# ADC.net
KiCad netlist of a schematic drawn in Altium Designer
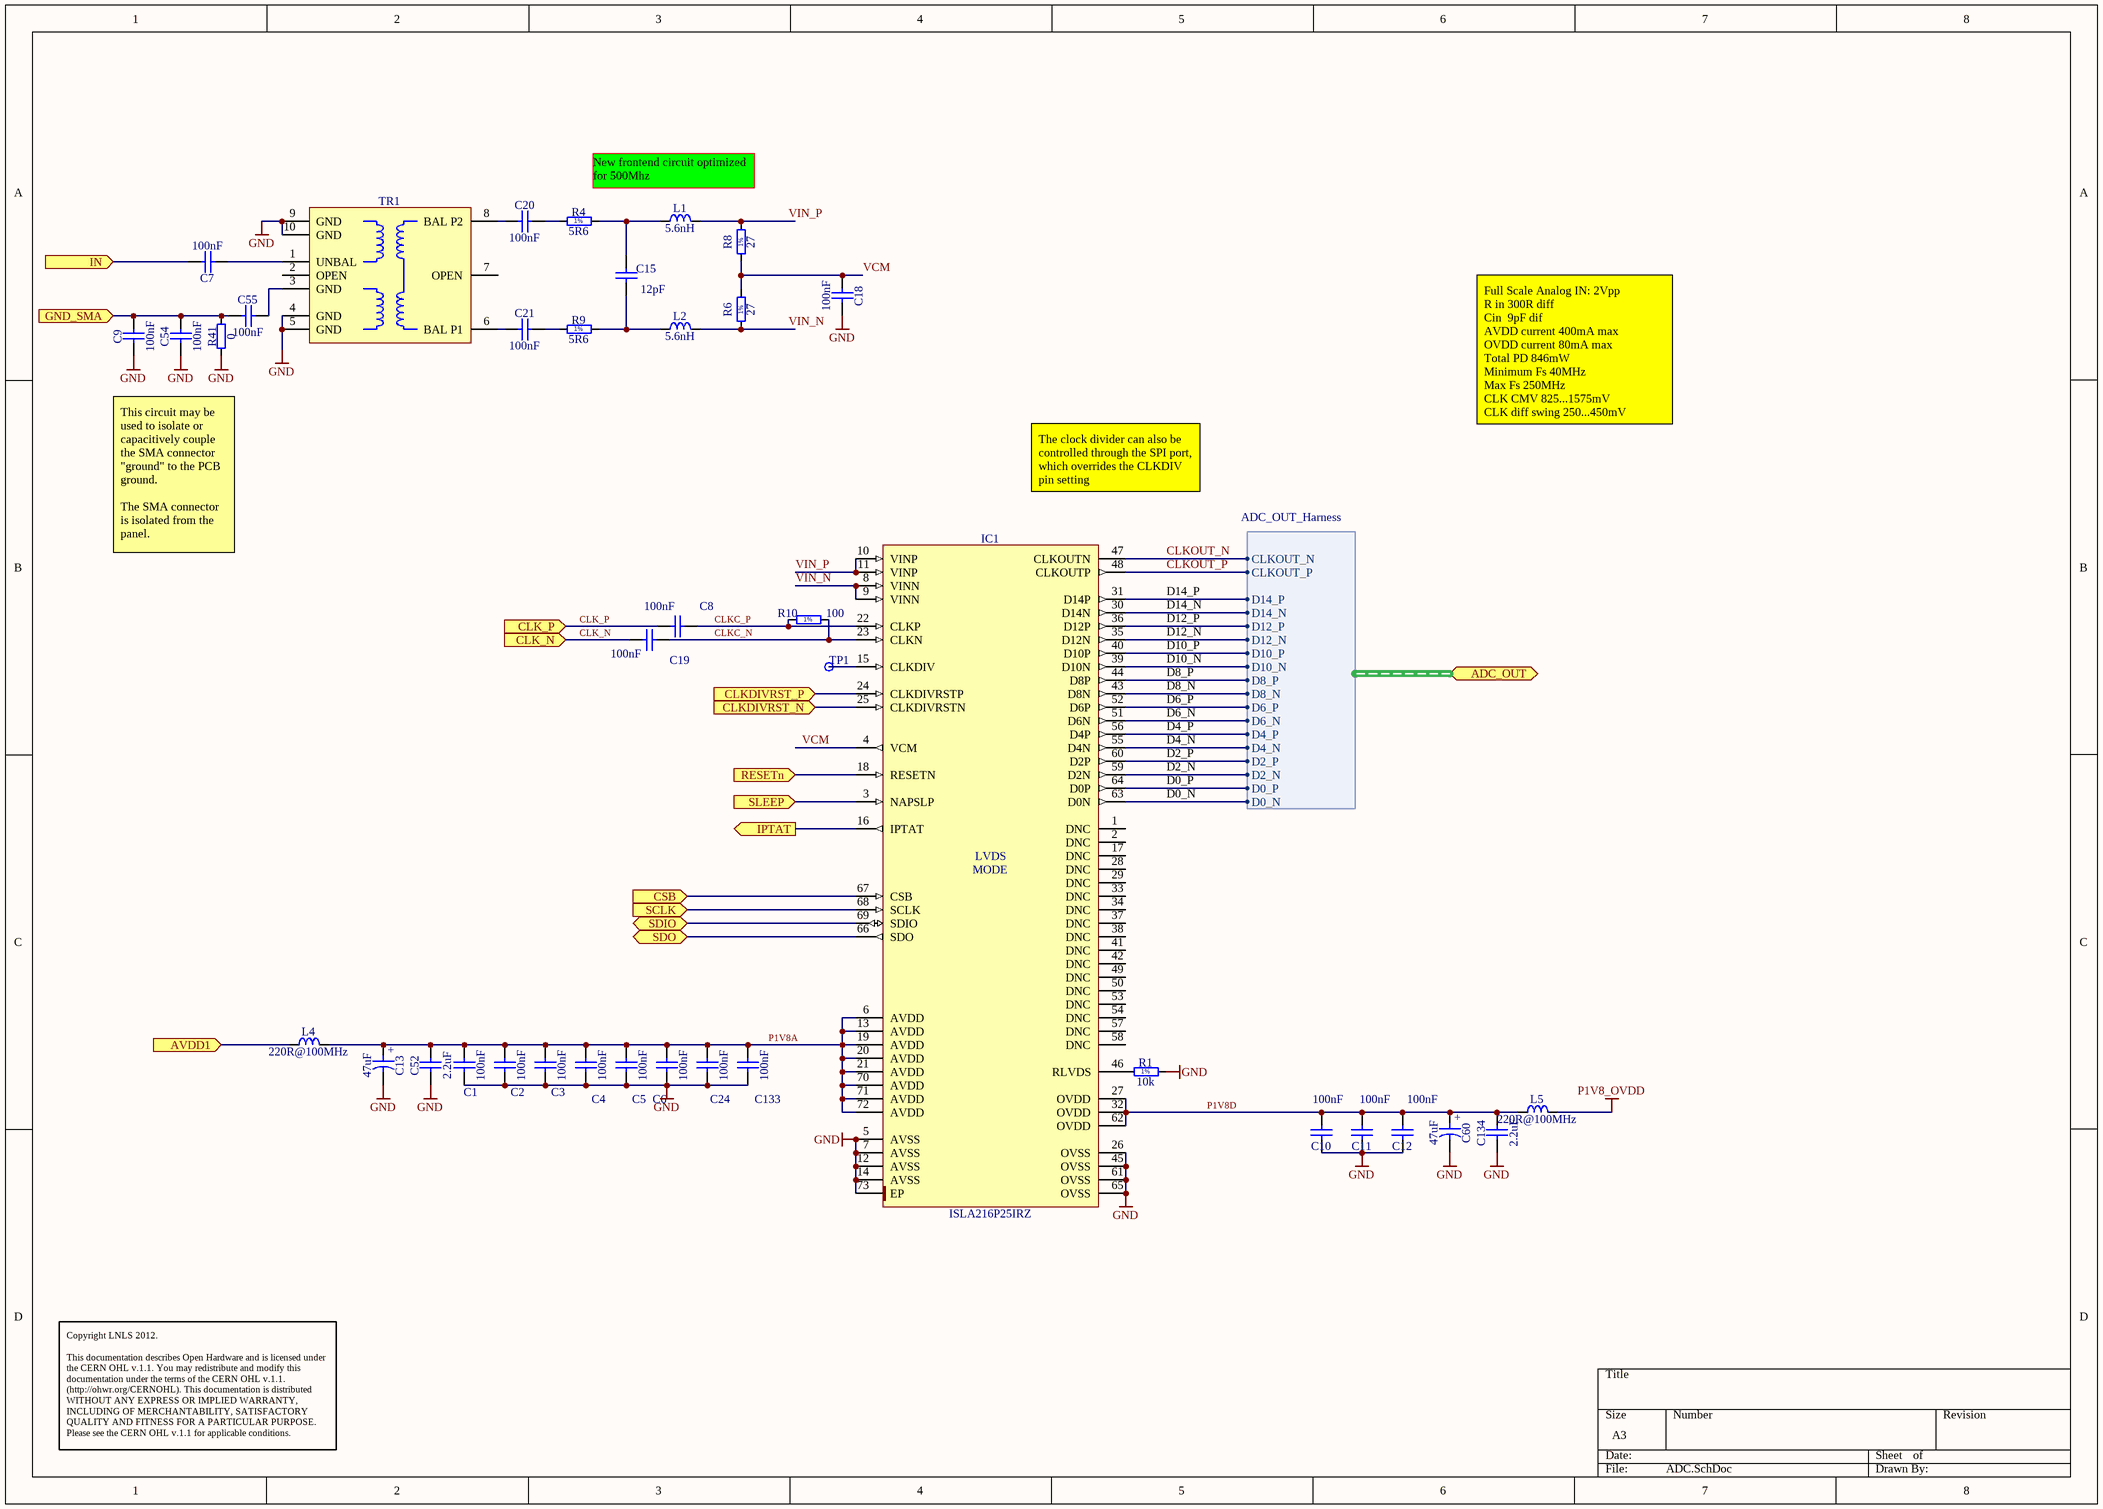
[diagram p0: ADC.SchDoc]

(export (version "E")
  (design (tool "Eeschema 10.0.6"))
  (components
    (comp (ref "C1")
      (value "100nF")
      (footprint "CAPC0603X33N")
      (description "Non-polarised capacitor")
      (fields
        (field (name "PART NUMBER") "CC0201_100NF_6.3V_10%_X5R")
        (field (name "VOLTAGE") "6.3V")
        (field (name "AUTHOR") "CERN DEM JLC")
      )
      (libsource (lib "Capacitors") (part "Capacitor - non polarized"))
    )
    (comp (ref "C2")
      (value "100nF")
      (footprint "CAPC0603X33N")
      (description "Non-polarised capacitor")
      (fields
        (field (name "PART NUMBER") "CC0201_100NF_6.3V_10%_X5R")
        (field (name "VOLTAGE") "6.3V")
        (field (name "AUTHOR") "CERN DEM JLC")
      )
      (libsource (lib "Capacitors") (part "Capacitor - non polarized"))
    )
    (comp (ref "C3")
      (value "100nF")
      (footprint "CAPC0603X33N")
      (description "Non-polarised capacitor")
      (fields
        (field (name "PART NUMBER") "CC0201_100NF_6.3V_10%_X5R")
        (field (name "VOLTAGE") "6.3V")
        (field (name "AUTHOR") "CERN DEM JLC")
      )
      (libsource (lib "Capacitors") (part "Capacitor - non polarized"))
    )
    (comp (ref "C4")
      (value "100nF")
      (footprint "CAPC0603X33N")
      (description "Non-polarised capacitor")
      (fields
        (field (name "PART NUMBER") "CC0201_100NF_6.3V_10%_X5R")
        (field (name "VOLTAGE") "6.3V")
        (field (name "AUTHOR") "CERN DEM JLC")
      )
      (libsource (lib "Capacitors") (part "Capacitor - non polarized"))
    )
    (comp (ref "C5")
      (value "100nF")
      (footprint "CAPC0603X33N")
      (description "Non-polarised capacitor")
      (fields
        (field (name "PART NUMBER") "CC0201_100NF_6.3V_10%_X5R")
        (field (name "VOLTAGE") "6.3V")
        (field (name "AUTHOR") "CERN DEM JLC")
      )
      (libsource (lib "Capacitors") (part "Capacitor - non polarized"))
    )
    (comp (ref "C6")
      (value "100nF")
      (footprint "CAPC0603X33N")
      (description "Non-polarised capacitor")
      (fields
        (field (name "PART NUMBER") "CC0201_100NF_6.3V_10%_X5R")
        (field (name "VOLTAGE") "6.3V")
        (field (name "AUTHOR") "CERN DEM JLC")
      )
      (libsource (lib "Capacitors") (part "Capacitor - non polarized"))
    )
    (comp (ref "C7")
      (value "100nF")
      (footprint "CAPC0603X33N")
      (description "Non-polarised capacitor")
      (fields
        (field (name "PART NUMBER") "CC0201_100NF_6.3V_10%_X5R")
        (field (name "VOLTAGE") "6.3V")
        (field (name "AUTHOR") "CERN DEM JLC")
      )
      (libsource (lib "Capacitors") (part "Capacitor - non polarized"))
    )
    (comp (ref "C8")
      (value "100nF")
      (footprint "CAPC0603X33N")
      (description "Non-polarised capacitor")
      (fields
        (field (name "PART NUMBER") "CC0201_100NF_6.3V_10%_X5R")
        (field (name "VOLTAGE") "6.3V")
        (field (name "AUTHOR") "CERN DEM JLC")
      )
      (libsource (lib "Capacitors") (part "Capacitor - non polarized"))
    )
    (comp (ref "C9")
      (value "100nF")
      (footprint "CAPC0603X33N")
      (description "Non-polarised capacitor")
      (fields
        (field (name "PART NUMBER") "CC0201_100NF_6.3V_10%_X5R")
        (field (name "VOLTAGE") "6.3V")
        (field (name "AUTHOR") "CERN DEM JLC")
      )
      (libsource (lib "Capacitors") (part "Capacitor - non polarized"))
    )
    (comp (ref "C10")
      (value "100nF")
      (footprint "CAPC0603X33N")
      (description "Non-polarised capacitor")
      (fields
        (field (name "PART NUMBER") "CC0201_100NF_6.3V_10%_X5R")
        (field (name "VOLTAGE") "6.3V")
        (field (name "AUTHOR") "CERN DEM JLC")
      )
      (libsource (lib "Capacitors") (part "Capacitor - non polarized"))
    )
    (comp (ref "C11")
      (value "100nF")
      (footprint "CAPC0603X33N")
      (description "Non-polarised capacitor")
      (fields
        (field (name "PART NUMBER") "CC0201_100NF_6.3V_10%_X5R")
        (field (name "VOLTAGE") "6.3V")
        (field (name "AUTHOR") "CERN DEM JLC")
      )
      (libsource (lib "Capacitors") (part "Capacitor - non polarized"))
    )
    (comp (ref "C12")
      (value "100nF")
      (footprint "CAPC0603X33N")
      (description "Non-polarised capacitor")
      (fields
        (field (name "PART NUMBER") "CC0201_100NF_6.3V_10%_X5R")
        (field (name "VOLTAGE") "6.3V")
        (field (name "AUTHOR") "CERN DEM JLC")
      )
      (libsource (lib "Capacitors") (part "Capacitor - non polarized"))
    )
    (comp (ref "C13")
      (value "47uF")
      (footprint "CAPMP3528X210N")
      (description "Polarised capacitor")
      (fields
        (field (name "PART NUMBER") "CTE3528-21_47UF_6.3V_10%_LESR0250")
        (field (name "VOLTAGE") "6.3V")
        (field (name "AUTHOR") "CERN DEM JLC")
      )
      (libsource (lib "Capacitors") (part "Capacitor - polarized"))
    )
    (comp (ref "C15")
      (value "12pF")
      (footprint "CAPC2012X135N")
      (description "Non-polarised capacitor")
      (fields
        (field (name "PART NUMBER") "CC0805_12PF_50V_5%_NP0")
        (field (name "VOLTAGE") "50V")
        (field (name "AUTHOR") "CERN DEM JLC")
      )
      (libsource (lib "Capacitors") (part "Capacitor - non polarized"))
    )
    (comp (ref "C18")
      (value "100nF")
      (footprint "CAPC0603X33N")
      (description "Non-polarised capacitor")
      (fields
        (field (name "PART NUMBER") "CC0201_100NF_6.3V_10%_X5R")
        (field (name "VOLTAGE") "6.3V")
        (field (name "AUTHOR") "CERN DEM JLC")
      )
      (libsource (lib "Capacitors") (part "Capacitor - non polarized"))
    )
    (comp (ref "C19")
      (value "100nF")
      (footprint "CAPC0603X33N")
      (description "Non-polarised capacitor")
      (fields
        (field (name "PART NUMBER") "CC0201_100NF_6.3V_10%_X5R")
        (field (name "VOLTAGE") "6.3V")
        (field (name "AUTHOR") "CERN DEM JLC")
      )
      (libsource (lib "Capacitors") (part "Capacitor - non polarized"))
    )
    (comp (ref "C20")
      (value "100nF")
      (footprint "CAPC0603X33N")
      (description "Non-polarised capacitor")
      (fields
        (field (name "PART NUMBER") "CC0201_100NF_6.3V_10%_X5R")
        (field (name "VOLTAGE") "6.3V")
        (field (name "AUTHOR") "CERN DEM JLC")
      )
      (libsource (lib "Capacitors") (part "Capacitor - non polarized"))
    )
    (comp (ref "C21")
      (value "100nF")
      (footprint "CAPC0603X33N")
      (description "Non-polarised capacitor")
      (fields
        (field (name "PART NUMBER") "CC0201_100NF_6.3V_10%_X5R")
        (field (name "VOLTAGE") "6.3V")
        (field (name "AUTHOR") "CERN DEM JLC")
      )
      (libsource (lib "Capacitors") (part "Capacitor - non polarized"))
    )
    (comp (ref "C24")
      (value "100nF")
      (footprint "CAPC0603X33N")
      (description "Non-polarised capacitor")
      (fields
        (field (name "PART NUMBER") "CC0201_100NF_6.3V_10%_X5R")
        (field (name "VOLTAGE") "6.3V")
        (field (name "AUTHOR") "CERN DEM JLC")
      )
      (libsource (lib "Capacitors") (part "Capacitor - non polarized"))
    )
    (comp (ref "C52")
      (value "2.2uF")
      (footprint "CAPC2012X135N")
      (description "Non-polarised capacitor")
      (fields
        (field (name "PART NUMBER") "CC0805_2.2UF_16V_10%_X7R")
        (field (name "VOLTAGE") "16V")
        (field (name "AUTHOR") "CERN DEM JLC")
      )
      (libsource (lib "Capacitors") (part "Capacitor - non polarized"))
    )
    (comp (ref "C54")
      (value "100nF")
      (footprint "CAPC0603X33N")
      (description "Non-polarised capacitor")
      (fields
        (field (name "PART NUMBER") "CC0201_100NF_6.3V_10%_X5R")
        (field (name "VOLTAGE") "6.3V")
        (field (name "AUTHOR") "CERN DEM JLC")
      )
      (libsource (lib "Capacitors") (part "Capacitor - non polarized"))
    )
    (comp (ref "C55")
      (value "100nF")
      (footprint "CAPC0603X33N")
      (description "Non-polarised capacitor")
      (fields
        (field (name "PART NUMBER") "CC0201_100NF_6.3V_10%_X5R")
        (field (name "VOLTAGE") "6.3V")
        (field (name "AUTHOR") "CERN DEM JLC")
      )
      (libsource (lib "Capacitors") (part "Capacitor - non polarized"))
    )
    (comp (ref "C60")
      (value "47uF")
      (footprint "CAPMP3528X210N")
      (description "Polarised capacitor")
      (fields
        (field (name "PART NUMBER") "CTE3528-21_47UF_6.3V_10%_LESR0250")
        (field (name "VOLTAGE") "6.3V")
        (field (name "AUTHOR") "CERN DEM JLC")
      )
      (libsource (lib "Capacitors") (part "Capacitor - polarized"))
    )
    (comp (ref "C133")
      (value "100nF")
      (footprint "CAPC0603X33N")
      (description "Non-polarised capacitor")
      (fields
        (field (name "PART NUMBER") "CC0201_100NF_6.3V_10%_X5R")
        (field (name "VOLTAGE") "6.3V")
        (field (name "AUTHOR") "CERN DEM JLC")
      )
      (libsource (lib "Capacitors") (part "Capacitor - non polarized"))
    )
    (comp (ref "C134")
      (value "2.2uF")
      (footprint "CAPC2012X135N")
      (description "Non-polarised capacitor")
      (fields
        (field (name "PART NUMBER") "CC0805_2.2UF_16V_10%_X7R")
        (field (name "VOLTAGE") "16V")
        (field (name "AUTHOR") "CERN DEM JLC")
      )
      (libsource (lib "Capacitors") (part "Capacitor - non polarized"))
    )
    (comp (ref "IC1")
      (value "ISLA216P25IRZ")
      (footprint "INTERSIL_L72.10x10E")
      (description "16-Bit, 250MSPS ADC (LVDS Mode)")
      (fields (field (name "MANUFACTURER") "INTERSIL") (field (name "AUTHOR") "CERN DEM JLC"))
      (libsource (lib "ICs And Semiconductors") (part "ISLA216P25IRZ_LVDS"))
    )
    (comp (ref "L1")
      (value "5.6nH")
      (footprint "INDC1005X55N")
      (description "Inductor")
      (fields
        (field (name "PART NUMBER") "IND0402_5.6nH_0.3n_JOHANSON_L-07C5N6SV6T")
        (field (name "POWER") "300mA")
        (field (name "AUTHOR") "LNLS DIG GBMB")
      )
      (libsource (lib "Inductors & Transformers") (part "Inductor"))
    )
    (comp (ref "L2")
      (value "5.6nH")
      (footprint "INDC1005X55N")
      (description "Inductor")
      (fields
        (field (name "PART NUMBER") "IND0402_5.6nH_0.3n_JOHANSON_L-07C5N6SV6T")
        (field (name "POWER") "300mA")
        (field (name "AUTHOR") "LNLS DIG GBMB")
      )
      (libsource (lib "Inductors & Transformers") (part "Inductor"))
    )
    (comp (ref "L4")
      (value "220R@100MHz")
      (footprint "INDC2012X105N")
      (description "Inductor")
      (fields
        (field (name "PART NUMBER") "IND0805_MURATA_BLM21PG221SN1D")
        (field (name "POWER") "2A")
        (field (name "AUTHOR") "CERN DEM JLC")
      )
      (libsource (lib "Inductors & Transformers") (part "Inductor"))
    )
    (comp (ref "L5")
      (value "220R@100MHz")
      (footprint "INDC2012X105N")
      (description "Inductor")
      (fields
        (field (name "PART NUMBER") "IND0805_MURATA_BLM21PG221SN1D")
        (field (name "POWER") "2A")
        (field (name "AUTHOR") "CERN DEM JLC")
      )
      (libsource (lib "Inductors & Transformers") (part "Inductor"))
    )
    (comp (ref "R1")
      (value "10k")
      (footprint "RESC1005X40N")
      (description "Resistor - 1%")
      (fields
        (field (name "PART NUMBER") "R0402_10K_1%_0.0625W_100PPM")
        (field (name "POWER") "0.0625W")
        (field (name "AUTHOR") "CERN DEM JLC")
      )
      (libsource (lib "Resistors") (part "Resistor - 1%"))
    )
    (comp (ref "R4")
      (value "5R6")
      (footprint "RESC1005X40N")
      (description "Resistor - 1%")
      (fields
        (field (name "PART NUMBER") "R0402_5R6_1%_0.0625W_200PPM")
        (field (name "POWER") "0.0625W")
        (field (name "AUTHOR") "CERN DEM JLC")
      )
      (libsource (lib "Resistors") (part "Resistor - 1%"))
    )
    (comp (ref "R6")
      (value "27")
      (footprint "RESC1005X40N")
      (description "Resistor - 1%")
      (fields
        (field (name "PART NUMBER") "RC0402FR-0720RL")
        (field (name "POWER") "0.0625W")
        (field (name "AUTHOR") "CERN DEM JLC")
      )
      (libsource (lib "Resistors") (part "Resistor - 1%"))
    )
    (comp (ref "R8")
      (value "27")
      (footprint "RESC1005X40N")
      (description "Resistor - 1%")
      (fields
        (field (name "PART NUMBER") "RC0402FR-0720RL")
        (field (name "POWER") "0.0625W")
        (field (name "AUTHOR") "CERN DEM JLC")
      )
      (libsource (lib "Resistors") (part "Resistor - 1%"))
    )
    (comp (ref "R9")
      (value "5R6")
      (footprint "RESC1005X40N")
      (description "Resistor - 1%")
      (fields
        (field (name "PART NUMBER") "R0402_5R6_1%_0.0625W_200PPM")
        (field (name "POWER") "0.0625W")
        (field (name "AUTHOR") "CERN DEM JLC")
      )
      (libsource (lib "Resistors") (part "Resistor - 1%"))
    )
    (comp (ref "R10")
      (value "100")
      (footprint "RESC1005X40N")
      (description "Resistor - 1%")
      (fields
        (field (name "PART NUMBER") "R0402_100R_1%_0.0625W_100PPM")
        (field (name "POWER") "0.0625W")
        (field (name "AUTHOR") "CERN DEM JLC")
      )
      (libsource (lib "Resistors") (part "Resistor - 1%"))
    )
    (comp (ref "R41")
      (value "0")
      (footprint "RESC0603X28N")
      (description "Resistor")
      (fields
        (field (name "PART NUMBER") "R0201_0R_JUMPER")
        (field (name "MANUFACTURER") "GENERIC")
        (field (name "AUTHOR") "CERN DEM JLC")
      )
      (libsource (lib "Resistors") (part "Resistor"))
    )
    (comp (ref "TP1")
      (value "~")
      (footprint "TPR120")
      (description "Test Point")
      (fields (field (name "PART NUMBER") "SMD_PAD_1.20_d_MM") (field (name "AUTHOR") "LNLS DIG GBMB"))
      (libsource (lib "Eletro-mechanical") (part "Test Point"))
    )
    (comp (ref "TR1")
      (value "~")
      (footprint "XFMR_ANAREN_BD0205F5050A00")
      (description "70MHz - 1000MHz Ultra Low Profile Sub-Miniature Balanced to Unbalanced Transformer")
      (fields
        (field (name "PART NUMBER") "XFMR_ANAREN_BD0205F5050A00")
        (field (name "MANUFACTURER") "ANAREN")
        (field (name "AUTHOR") "CERN DEM JLC")
      )
      (libsource (lib "Inductors & Transformers") (part "XFMR_ANAREN_BD0205F5050A00"))
    )
  )
  (nets
    (net (code "2") (name "/AVDD1") (class "Default")
      (node (ref "L4") (pin "1") (pinfunction "1_1") (pintype "passive"))
    )
    (net (code "3") (name "/CLKC_N") (class "Default")
      (node (ref "C19") (pin "2") (pinfunction "2_2") (pintype "passive"))
      (node (ref "IC1") (pin "23") (pinfunction "CLKN_23") (pintype "input"))
      (node (ref "R10") (pin "2") (pinfunction "2_2") (pintype "passive"))
    )
    (net (code "4") (name "/CLKC_P") (class "Default")
      (node (ref "C8") (pin "2") (pinfunction "2_2") (pintype "passive"))
      (node (ref "IC1") (pin "22") (pinfunction "CLKP_22") (pintype "input"))
      (node (ref "R10") (pin "1") (pinfunction "1_1") (pintype "passive"))
    )
    (net (code "5") (name "/CLKDIVRST_N") (class "Default")
      (node (ref "IC1") (pin "25") (pinfunction "CLKDIVRSTN_25") (pintype "input"))
    )
    (net (code "6") (name "/CLKDIVRST_P") (class "Default")
      (node (ref "IC1") (pin "24") (pinfunction "CLKDIVRSTP_24") (pintype "input"))
    )
    (net (code "7") (name "/CLKOUT_N") (class "Default")
      (node (ref "IC1") (pin "47") (pinfunction "CLKOUTN_47") (pintype "open_collector"))
    )
    (net (code "8") (name "/CLKOUT_P") (class "Default")
      (node (ref "IC1") (pin "48") (pinfunction "CLKOUTP_48") (pintype "output"))
    )
    (net (code "9") (name "/CLK_N") (class "Default")
      (node (ref "C19") (pin "1") (pinfunction "1_1") (pintype "passive"))
    )
    (net (code "10") (name "/CLK_P") (class "Default")
      (node (ref "C8") (pin "1") (pinfunction "1_1") (pintype "passive"))
    )
    (net (code "11") (name "/CSB") (class "Default")
      (node (ref "IC1") (pin "67") (pinfunction "CSB_67") (pintype "input"))
    )
    (net (code "12") (name "/D0_N") (class "Default")
      (node (ref "IC1") (pin "63") (pinfunction "D0N_63") (pintype "output"))
    )
    (net (code "13") (name "/D0_P") (class "Default")
      (node (ref "IC1") (pin "64") (pinfunction "D0P_64") (pintype "output"))
    )
    (net (code "14") (name "/D2_N") (class "Default")
      (node (ref "IC1") (pin "59") (pinfunction "D2N_59") (pintype "output"))
    )
    (net (code "15") (name "/D2_P") (class "Default")
      (node (ref "IC1") (pin "60") (pinfunction "D2P_60") (pintype "output"))
    )
    (net (code "16") (name "/D4_N") (class "Default")
      (node (ref "IC1") (pin "55") (pinfunction "D4N_55") (pintype "output"))
    )
    (net (code "17") (name "/D4_P") (class "Default")
      (node (ref "IC1") (pin "56") (pinfunction "D4P_56") (pintype "output"))
    )
    (net (code "18") (name "/D6_N") (class "Default")
      (node (ref "IC1") (pin "51") (pinfunction "D6N_51") (pintype "output"))
    )
    (net (code "19") (name "/D6_P") (class "Default")
      (node (ref "IC1") (pin "52") (pinfunction "D6P_52") (pintype "output"))
    )
    (net (code "20") (name "/D8_N") (class "Default")
      (node (ref "IC1") (pin "43") (pinfunction "D8N_43") (pintype "output"))
    )
    (net (code "21") (name "/D8_P") (class "Default")
      (node (ref "IC1") (pin "44") (pinfunction "D8P_44") (pintype "output"))
    )
    (net (code "22") (name "/D10_N") (class "Default")
      (node (ref "IC1") (pin "39") (pinfunction "D10N_39") (pintype "output"))
    )
    (net (code "23") (name "/D10_P") (class "Default")
      (node (ref "IC1") (pin "40") (pinfunction "D10P_40") (pintype "output"))
    )
    (net (code "24") (name "/D12_N") (class "Default")
      (node (ref "IC1") (pin "35") (pinfunction "D12N_35") (pintype "output"))
    )
    (net (code "25") (name "/D12_P") (class "Default")
      (node (ref "IC1") (pin "36") (pinfunction "D12P_36") (pintype "output"))
    )
    (net (code "26") (name "/D14_N") (class "Default")
      (node (ref "IC1") (pin "30") (pinfunction "D14N_30") (pintype "output"))
    )
    (net (code "27") (name "/D14_P") (class "Default")
      (node (ref "IC1") (pin "31") (pinfunction "D14P_31") (pintype "output"))
    )
    (net (code "28") (name "/GND_SMA") (class "Default")
      (node (ref "C54") (pin "2") (pinfunction "2_2") (pintype "passive"))
      (node (ref "C55") (pin "1") (pinfunction "1_1") (pintype "passive"))
      (node (ref "C9") (pin "2") (pinfunction "2_2") (pintype "passive"))
      (node (ref "R41") (pin "2") (pinfunction "2_2") (pintype "passive"))
    )
    (net (code "29") (name "/IN") (class "Default")
      (node (ref "C7") (pin "2") (pinfunction "2_2") (pintype "passive"))
    )
    (net (code "30") (name "/IPTAT") (class "Default")
      (node (ref "IC1") (pin "16") (pinfunction "IPTAT_16") (pintype "output"))
    )
    (net (code "31") (name "/P1V8A") (class "Default")
      (node (ref "C1") (pin "2") (pinfunction "2_2") (pintype "passive"))
      (node (ref "C13") (pin "1") (pinfunction "1_1") (pintype "passive"))
      (node (ref "C133") (pin "2") (pinfunction "2_2") (pintype "passive"))
      (node (ref "C2") (pin "2") (pinfunction "2_2") (pintype "passive"))
      (node (ref "C24") (pin "2") (pinfunction "2_2") (pintype "passive"))
      (node (ref "C3") (pin "2") (pinfunction "2_2") (pintype "passive"))
      (node (ref "C4") (pin "2") (pinfunction "2_2") (pintype "passive"))
      (node (ref "C5") (pin "2") (pinfunction "2_2") (pintype "passive"))
      (node (ref "C52") (pin "2") (pinfunction "2_2") (pintype "passive"))
      (node (ref "C6") (pin "2") (pinfunction "2_2") (pintype "passive"))
      (node (ref "IC1") (pin "13") (pinfunction "AVDD_13") (pintype "power_in"))
      (node (ref "IC1") (pin "19") (pinfunction "AVDD_19") (pintype "power_in"))
      (node (ref "IC1") (pin "20") (pinfunction "AVDD_20") (pintype "power_in"))
      (node (ref "IC1") (pin "21") (pinfunction "AVDD_21") (pintype "power_in"))
      (node (ref "IC1") (pin "6") (pinfunction "AVDD_6") (pintype "power_in"))
      (node (ref "IC1") (pin "70") (pinfunction "AVDD_70") (pintype "power_in"))
      (node (ref "IC1") (pin "71") (pinfunction "AVDD_71") (pintype "power_in"))
      (node (ref "IC1") (pin "72") (pinfunction "AVDD_72") (pintype "power_in"))
      (node (ref "L4") (pin "2") (pinfunction "2_2") (pintype "passive"))
    )
    (net (code "32") (name "/P1V8D") (class "Default")
      (node (ref "C10") (pin "2") (pinfunction "2_2") (pintype "passive"))
      (node (ref "C11") (pin "2") (pinfunction "2_2") (pintype "passive"))
      (node (ref "C12") (pin "2") (pinfunction "2_2") (pintype "passive"))
      (node (ref "C134") (pin "2") (pinfunction "2_2") (pintype "passive"))
      (node (ref "C60") (pin "1") (pinfunction "1_1") (pintype "passive"))
      (node (ref "IC1") (pin "27") (pinfunction "OVDD_27") (pintype "power_in"))
      (node (ref "IC1") (pin "32") (pinfunction "OVDD_32") (pintype "power_in"))
      (node (ref "IC1") (pin "62") (pinfunction "OVDD_62") (pintype "power_in"))
      (node (ref "L5") (pin "1") (pinfunction "1_1") (pintype "passive"))
    )
    (net (code "33") (name "/RESETn") (class "Default")
      (node (ref "IC1") (pin "18") (pinfunction "RESETN_18") (pintype "input"))
    )
    (net (code "34") (name "/SCLK") (class "Default")
      (node (ref "IC1") (pin "68") (pinfunction "SCLK_68") (pintype "input"))
    )
    (net (code "35") (name "/SDIO") (class "Default")
      (node (ref "IC1") (pin "69") (pinfunction "SDIO_69") (pintype "bidirectional"))
    )
    (net (code "36") (name "/SDO") (class "Default")
      (node (ref "IC1") (pin "66") (pinfunction "SDO_66") (pintype "output"))
    )
    (net (code "37") (name "/SLEEP") (class "Default")
      (node (ref "IC1") (pin "3") (pinfunction "NAPSLP_3") (pintype "input"))
    )
    (net (code "38") (name "/VCM") (class "Default")
      (node (ref "C18") (pin "1") (pinfunction "1_1") (pintype "passive"))
      (node (ref "IC1") (pin "4") (pinfunction "VCM_4") (pintype "output"))
      (node (ref "R6") (pin "2") (pinfunction "2_2") (pintype "passive"))
      (node (ref "R8") (pin "1") (pinfunction "1_1") (pintype "passive"))
    )
    (net (code "39") (name "/VIN_N") (class "Default")
      (node (ref "IC1") (pin "8") (pinfunction "VINN_8") (pintype "input"))
      (node (ref "IC1") (pin "9") (pinfunction "VINN_9") (pintype "input"))
      (node (ref "L2") (pin "2") (pinfunction "2_2") (pintype "passive"))
      (node (ref "R6") (pin "1") (pinfunction "1_1") (pintype "passive"))
    )
    (net (code "40") (name "/VIN_P") (class "Default")
      (node (ref "IC1") (pin "10") (pinfunction "VINP_10") (pintype "input"))
      (node (ref "IC1") (pin "11") (pinfunction "VINP_11") (pintype "input"))
      (node (ref "L1") (pin "2") (pinfunction "2_2") (pintype "passive"))
      (node (ref "R8") (pin "2") (pinfunction "2_2") (pintype "passive"))
    )
    (net (code "42") (name "GND") (class "Default")
      (node (ref "C1") (pin "1") (pinfunction "1_1") (pintype "passive"))
      (node (ref "C10") (pin "1") (pinfunction "1_1") (pintype "passive"))
      (node (ref "C11") (pin "1") (pinfunction "1_1") (pintype "passive"))
      (node (ref "C12") (pin "1") (pinfunction "1_1") (pintype "passive"))
      (node (ref "C13") (pin "2") (pinfunction "2_2") (pintype "passive"))
      (node (ref "C133") (pin "1") (pinfunction "1_1") (pintype "passive"))
      (node (ref "C134") (pin "1") (pinfunction "1_1") (pintype "passive"))
      (node (ref "C18") (pin "2") (pinfunction "2_2") (pintype "passive"))
      (node (ref "C2") (pin "1") (pinfunction "1_1") (pintype "passive"))
      (node (ref "C24") (pin "1") (pinfunction "1_1") (pintype "passive"))
      (node (ref "C3") (pin "1") (pinfunction "1_1") (pintype "passive"))
      (node (ref "C4") (pin "1") (pinfunction "1_1") (pintype "passive"))
      (node (ref "C5") (pin "1") (pinfunction "1_1") (pintype "passive"))
      (node (ref "C52") (pin "1") (pinfunction "1_1") (pintype "passive"))
      (node (ref "C54") (pin "1") (pinfunction "1_1") (pintype "passive"))
      (node (ref "C6") (pin "1") (pinfunction "1_1") (pintype "passive"))
      (node (ref "C60") (pin "2") (pinfunction "2_2") (pintype "passive"))
      (node (ref "C9") (pin "1") (pinfunction "1_1") (pintype "passive"))
      (node (ref "IC1") (pin "12") (pinfunction "AVSS_12") (pintype "power_in"))
      (node (ref "IC1") (pin "14") (pinfunction "AVSS_14") (pintype "power_in"))
      (node (ref "IC1") (pin "26") (pinfunction "OVSS_26") (pintype "power_in"))
      (node (ref "IC1") (pin "45") (pinfunction "OVSS_45") (pintype "power_in"))
      (node (ref "IC1") (pin "5") (pinfunction "AVSS_5") (pintype "power_in"))
      (node (ref "IC1") (pin "61") (pinfunction "OVSS_61") (pintype "power_in"))
      (node (ref "IC1") (pin "65") (pinfunction "OVSS_65") (pintype "power_in"))
      (node (ref "IC1") (pin "7") (pinfunction "AVSS_7") (pintype "power_in"))
      (node (ref "IC1") (pin "73") (pinfunction "EP_73") (pintype "power_in"))
      (node (ref "R1") (pin "2") (pinfunction "2_2") (pintype "passive"))
      (node (ref "R41") (pin "1") (pinfunction "1_1") (pintype "passive"))
      (node (ref "TR1") (pin "10") (pinfunction "GND_10") (pintype "power_in"))
      (node (ref "TR1") (pin "4") (pinfunction "GND_4") (pintype "power_in"))
      (node (ref "TR1") (pin "5") (pinfunction "GND_5") (pintype "power_in"))
      (node (ref "TR1") (pin "9") (pinfunction "GND_9") (pintype "power_in"))
    )
    (net (code "43") (name "Net-(C15-Pad1)") (class "Default")
      (node (ref "C15") (pin "1") (pinfunction "1_1") (pintype "passive"))
      (node (ref "L2") (pin "1") (pinfunction "1_1") (pintype "passive"))
      (node (ref "R9") (pin "2") (pinfunction "2_2") (pintype "passive"))
    )
    (net (code "44") (name "Net-(C15-Pad2)") (class "Default")
      (node (ref "C15") (pin "2") (pinfunction "2_2") (pintype "passive"))
      (node (ref "L1") (pin "1") (pinfunction "1_1") (pintype "passive"))
      (node (ref "R4") (pin "2") (pinfunction "2_2") (pintype "passive"))
    )
    (net (code "45") (name "Net-(C20-Pad2)") (class "Default")
      (node (ref "C20") (pin "2") (pinfunction "2_2") (pintype "passive"))
      (node (ref "R4") (pin "1") (pinfunction "1_1") (pintype "passive"))
    )
    (net (code "46") (name "Net-(C21-Pad2)") (class "Default")
      (node (ref "C21") (pin "2") (pinfunction "2_2") (pintype "passive"))
      (node (ref "R9") (pin "1") (pinfunction "1_1") (pintype "passive"))
    )
    (net (code "47") (name "Net-(C55-Pad2)") (class "Default")
      (node (ref "C55") (pin "2") (pinfunction "2_2") (pintype "passive"))
      (node (ref "TR1") (pin "3") (pinfunction "GND_3") (pintype "power_in"))
    )
    (net (code "48") (name "Net-(IC1-CLKDIV)") (class "Default")
      (node (ref "IC1") (pin "15") (pinfunction "CLKDIV_15") (pintype "input"))
      (node (ref "TP1") (pin "1") (pinfunction "1_1") (pintype "bidirectional"))
    )
    (net (code "49") (name "Net-(IC1-RLVDS)") (class "Default")
      (node (ref "IC1") (pin "46") (pinfunction "RLVDS_46") (pintype "passive"))
      (node (ref "R1") (pin "1") (pinfunction "1_1") (pintype "passive"))
    )
    (net (code "50") (name "Net-(TR1-BAL_P1)") (class "Default")
      (node (ref "C21") (pin "1") (pinfunction "1_1") (pintype "passive"))
      (node (ref "TR1") (pin "6") (pinfunction "BAL_P1_6") (pintype "passive"))
    )
    (net (code "51") (name "Net-(TR1-BAL_P2)") (class "Default")
      (node (ref "C20") (pin "1") (pinfunction "1_1") (pintype "passive"))
      (node (ref "TR1") (pin "8") (pinfunction "BAL_P2_8") (pintype "passive"))
    )
    (net (code "52") (name "Net-(TR1-UNBAL)") (class "Default")
      (node (ref "C7") (pin "1") (pinfunction "1_1") (pintype "passive"))
      (node (ref "TR1") (pin "1") (pinfunction "UNBAL_1") (pintype "passive"))
    )
    (net (code "53") (name "P1V8_OVDD") (class "Default")
      (node (ref "L5") (pin "2") (pinfunction "2_2") (pintype "passive"))
    )
    (net (code "54") (name "unconnected-(IC1-DNC-Pad1)") (class "Default")
      (node (ref "IC1") (pin "1") (pinfunction "DNC_1") (pintype "passive"))
    )
    (net (code "55") (name "unconnected-(IC1-DNC-Pad2)") (class "Default")
      (node (ref "IC1") (pin "2") (pinfunction "DNC_2") (pintype "passive"))
    )
    (net (code "56") (name "unconnected-(IC1-DNC-Pad17)") (class "Default")
      (node (ref "IC1") (pin "17") (pinfunction "DNC_17") (pintype "passive"))
    )
    (net (code "57") (name "unconnected-(IC1-DNC-Pad28)") (class "Default")
      (node (ref "IC1") (pin "28") (pinfunction "DNC_28") (pintype "passive"))
    )
    (net (code "58") (name "unconnected-(IC1-DNC-Pad29)") (class "Default")
      (node (ref "IC1") (pin "29") (pinfunction "DNC_29") (pintype "passive"))
    )
    (net (code "59") (name "unconnected-(IC1-DNC-Pad33)") (class "Default")
      (node (ref "IC1") (pin "33") (pinfunction "DNC_33") (pintype "passive"))
    )
    (net (code "60") (name "unconnected-(IC1-DNC-Pad34)") (class "Default")
      (node (ref "IC1") (pin "34") (pinfunction "DNC_34") (pintype "passive"))
    )
    (net (code "61") (name "unconnected-(IC1-DNC-Pad37)") (class "Default")
      (node (ref "IC1") (pin "37") (pinfunction "DNC_37") (pintype "passive"))
    )
    (net (code "62") (name "unconnected-(IC1-DNC-Pad38)") (class "Default")
      (node (ref "IC1") (pin "38") (pinfunction "DNC_38") (pintype "passive"))
    )
    (net (code "63") (name "unconnected-(IC1-DNC-Pad41)") (class "Default")
      (node (ref "IC1") (pin "41") (pinfunction "DNC_41") (pintype "passive"))
    )
    (net (code "64") (name "unconnected-(IC1-DNC-Pad42)") (class "Default")
      (node (ref "IC1") (pin "42") (pinfunction "DNC_42") (pintype "passive"))
    )
    (net (code "65") (name "unconnected-(IC1-DNC-Pad49)") (class "Default")
      (node (ref "IC1") (pin "49") (pinfunction "DNC_49") (pintype "passive"))
    )
    (net (code "66") (name "unconnected-(IC1-DNC-Pad50)") (class "Default")
      (node (ref "IC1") (pin "50") (pinfunction "DNC_50") (pintype "passive"))
    )
    (net (code "67") (name "unconnected-(IC1-DNC-Pad53)") (class "Default")
      (node (ref "IC1") (pin "53") (pinfunction "DNC_53") (pintype "passive"))
    )
    (net (code "68") (name "unconnected-(IC1-DNC-Pad54)") (class "Default")
      (node (ref "IC1") (pin "54") (pinfunction "DNC_54") (pintype "passive"))
    )
    (net (code "69") (name "unconnected-(IC1-DNC-Pad57)") (class "Default")
      (node (ref "IC1") (pin "57") (pinfunction "DNC_57") (pintype "passive"))
    )
    (net (code "70") (name "unconnected-(IC1-DNC-Pad58)") (class "Default")
      (node (ref "IC1") (pin "58") (pinfunction "DNC_58") (pintype "passive"))
    )
    (net (code "71") (name "unconnected-(TR1-OPEN-Pad2)") (class "Default")
      (node (ref "TR1") (pin "2") (pinfunction "OPEN_2") (pintype "passive"))
    )
    (net (code "72") (name "unconnected-(TR1-OPEN-Pad7)") (class "Default")
      (node (ref "TR1") (pin "7") (pinfunction "OPEN_7") (pintype "passive"))
    )
  )
)
